# design.net
KiCad netlist of a schematic drawn in EAGLE
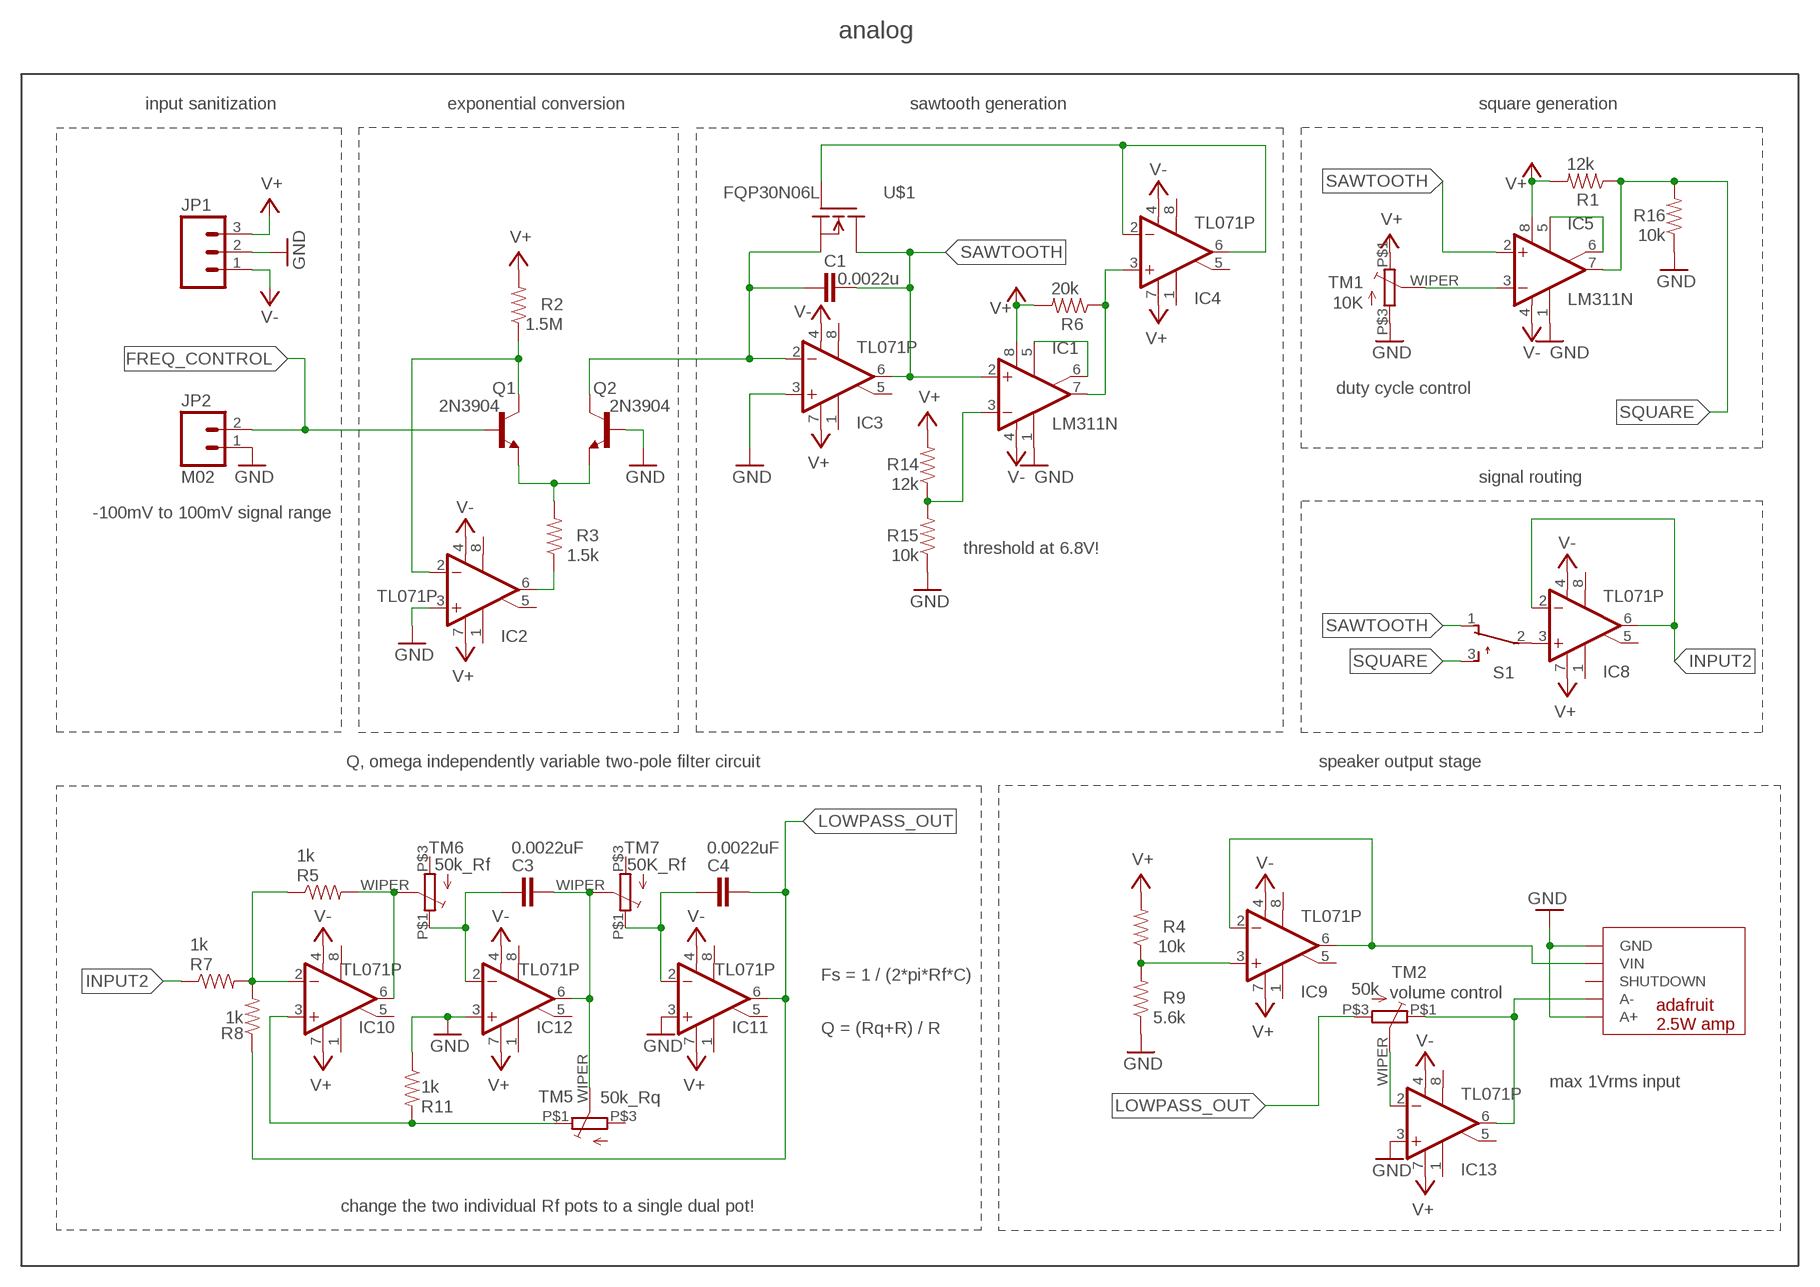
[diagram p0: schematic, sheet 1]

(export (version "E")
  (design (tool "Eeschema 10.0.6"))
  (components
    (comp (ref "C1")
      (value "0.0022u")
      (footprint "eagle-import:3872_WIMA_CAP")
      (libsource (lib "eagle-import") (part "CAPCAP_WIMA"))
    )
    (comp (ref "C3")
      (value "0.0022uF")
      (footprint "eagle-import:CAP-PTH-5MM")
      (libsource (lib "eagle-import") (part "CAPPTH1"))
    )
    (comp (ref "C4")
      (value "0.0022uF")
      (footprint "eagle-import:CAP-PTH-5MM")
      (libsource (lib "eagle-import") (part "CAPPTH1"))
    )
    (comp (ref "IC1")
      (value "LM311N")
      (footprint "eagle-import:DIL08")
      (libsource (lib "eagle-import") (part "LM311N"))
    )
    (comp (ref "IC2")
      (value "TL071P")
      (footprint "eagle-import:DIL08")
      (libsource (lib "eagle-import") (part "TL071P"))
    )
    (comp (ref "IC3")
      (value "TL071P")
      (footprint "eagle-import:DIL08")
      (libsource (lib "eagle-import") (part "TL071P"))
    )
    (comp (ref "IC4")
      (value "TL071P")
      (footprint "eagle-import:DIL08")
      (libsource (lib "eagle-import") (part "TL071P"))
    )
    (comp (ref "IC5")
      (value "LM311N")
      (footprint "eagle-import:DIL08")
      (libsource (lib "eagle-import") (part "LM311N"))
    )
    (comp (ref "IC8")
      (value "TL071P")
      (footprint "eagle-import:DIL08")
      (libsource (lib "eagle-import") (part "TL071P"))
    )
    (comp (ref "IC9")
      (value "TL071P")
      (footprint "eagle-import:DIL08")
      (libsource (lib "eagle-import") (part "TL071P"))
    )
    (comp (ref "IC10")
      (value "TL071P")
      (footprint "eagle-import:DIL08")
      (libsource (lib "eagle-import") (part "TL071P"))
    )
    (comp (ref "IC11")
      (value "TL071P")
      (footprint "eagle-import:DIL08")
      (libsource (lib "eagle-import") (part "TL071P"))
    )
    (comp (ref "IC12")
      (value "TL071P")
      (footprint "eagle-import:DIL08")
      (libsource (lib "eagle-import") (part "TL071P"))
    )
    (comp (ref "IC13")
      (value "TL071P")
      (footprint "eagle-import:DIL08")
      (libsource (lib "eagle-import") (part "TL071P"))
    )
    (comp (ref "JP1")
      (value "M03")
      (footprint "eagle-import:1X03")
      (libsource (lib "eagle-import") (part "M03"))
    )
    (comp (ref "JP2")
      (value "M02")
      (footprint "eagle-import:1X02")
      (libsource (lib "eagle-import") (part "M02"))
    )
    (comp (ref "Q1")
      (value "2N3904")
      (footprint "eagle-import:TO92")
      (libsource (lib "eagle-import") (part "2N3904"))
    )
    (comp (ref "Q2")
      (value "2N3904")
      (footprint "eagle-import:TO92")
      (libsource (lib "eagle-import") (part "2N3904"))
    )
    (comp (ref "R1")
      (value "12k")
      (footprint "eagle-import:AXIAL-0.3")
      (libsource (lib "eagle-import") (part "RESISTORAXIAL-0.3"))
    )
    (comp (ref "R2")
      (value "1.5M")
      (footprint "eagle-import:AXIAL-0.3")
      (libsource (lib "eagle-import") (part "RESISTORAXIAL-0.3"))
    )
    (comp (ref "R3")
      (value "1.5k")
      (footprint "eagle-import:AXIAL-0.3")
      (libsource (lib "eagle-import") (part "RESISTORAXIAL-0.3"))
    )
    (comp (ref "R4")
      (value "10k")
      (footprint "eagle-import:AXIAL-0.3")
      (libsource (lib "eagle-import") (part "RESISTORAXIAL-0.3"))
    )
    (comp (ref "R5")
      (value "1k")
      (footprint "eagle-import:AXIAL-0.3")
      (libsource (lib "eagle-import") (part "RESISTORAXIAL-0.3"))
    )
    (comp (ref "R6")
      (value "20k")
      (footprint "eagle-import:AXIAL-0.3")
      (libsource (lib "eagle-import") (part "RESISTORAXIAL-0.3"))
    )
    (comp (ref "R7")
      (value "1k")
      (footprint "eagle-import:AXIAL-0.3")
      (libsource (lib "eagle-import") (part "RESISTORAXIAL-0.3"))
    )
    (comp (ref "R8")
      (value "1k")
      (footprint "eagle-import:AXIAL-0.3")
      (libsource (lib "eagle-import") (part "RESISTORAXIAL-0.3"))
    )
    (comp (ref "R9")
      (value "5.6k")
      (footprint "eagle-import:AXIAL-0.3")
      (libsource (lib "eagle-import") (part "RESISTORAXIAL-0.3"))
    )
    (comp (ref "R11")
      (value "1k")
      (footprint "eagle-import:AXIAL-0.3")
      (libsource (lib "eagle-import") (part "RESISTORAXIAL-0.3"))
    )
    (comp (ref "R14")
      (value "12k")
      (footprint "eagle-import:AXIAL-0.3")
      (libsource (lib "eagle-import") (part "RESISTORAXIAL-0.3"))
    )
    (comp (ref "R15")
      (value "10k")
      (footprint "eagle-import:AXIAL-0.3")
      (libsource (lib "eagle-import") (part "RESISTORAXIAL-0.3"))
    )
    (comp (ref "R16")
      (value "10k")
      (footprint "eagle-import:AXIAL-0.3")
      (libsource (lib "eagle-import") (part "RESISTORAXIAL-0.3"))
    )
    (comp (ref "S1")
      (value "TL32PO")
      (footprint "eagle-import:TL3XPO")
      (libsource (lib "eagle-import") (part "TL32PO"))
    )
    (comp (ref "TM1")
      (value "10K")
      (footprint "eagle-import:3386_TRI")
      (libsource (lib "eagle-import") (part "TRIMPOT"))
    )
    (comp (ref "TM2")
      (value "50k")
      (footprint "eagle-import:3386_TRI")
      (libsource (lib "eagle-import") (part "TRIMPOT"))
    )
    (comp (ref "TM5")
      (value "50k_Rq")
      (footprint "eagle-import:3386_TRI")
      (libsource (lib "eagle-import") (part "TRIMPOT"))
    )
    (comp (ref "TM6")
      (value "50k_Rf")
      (footprint "eagle-import:3386_TRI")
      (libsource (lib "eagle-import") (part "TRIMPOT"))
    )
    (comp (ref "TM7")
      (value "50K_Rf")
      (footprint "eagle-import:3386_TRI")
      (libsource (lib "eagle-import") (part "TRIMPOT"))
    )
    (comp (ref "U$1")
      (value "FQP30N06L")
      (footprint "eagle-import:TO-220")
      (libsource (lib "eagle-import") (part "FQP30N06L"))
    )
    (comp (ref "U$2")
      (value "PAM8302A_ADAFRUIT")
      (footprint "eagle-import:PAM8302A_ADAFRUIT")
      (libsource (lib "eagle-import") (part "PAM8302A_ADAFRUIT"))
    )
  )
  (nets
    (net (code "1") (name "FREQ_CONTROL") (class "Default")
      (node (ref "JP2") (pin "2") (pinfunction "2_2") (pintype "passive"))
      (node (ref "Q1") (pin "2") (pinfunction "B_2") (pintype "passive"))
    )
    (net (code "2") (name "GND") (class "Default")
      (node (ref "IC1") (pin "1") (pinfunction "GND_1") (pintype "passive"))
      (node (ref "IC11") (pin "3") (pinfunction "+IN_3") (pintype "input"))
      (node (ref "IC12") (pin "3") (pinfunction "+IN_3") (pintype "input"))
      (node (ref "IC13") (pin "3") (pinfunction "+IN_3") (pintype "input"))
      (node (ref "IC2") (pin "3") (pinfunction "+IN_3") (pintype "input"))
      (node (ref "IC3") (pin "3") (pinfunction "+IN_3") (pintype "input"))
      (node (ref "IC5") (pin "1") (pinfunction "GND_1") (pintype "passive"))
      (node (ref "JP1") (pin "2") (pinfunction "2_2") (pintype "passive"))
      (node (ref "JP2") (pin "1") (pinfunction "1_1") (pintype "passive"))
      (node (ref "Q2") (pin "2") (pinfunction "B_2") (pintype "passive"))
      (node (ref "R11") (pin "P$1") (pinfunction "1_P$1") (pintype "passive"))
      (node (ref "R15") (pin "P$1") (pinfunction "1_P$1") (pintype "passive"))
      (node (ref "R16") (pin "P$1") (pinfunction "1_P$1") (pintype "passive"))
      (node (ref "R9") (pin "P$1") (pinfunction "1_P$1") (pintype "passive"))
      (node (ref "TM1") (pin "P$3") (pinfunction "A_P$3") (pintype "passive"))
      (node (ref "U$2") (pin "A+") (pinfunction "A+_A+") (pintype "bidirectional"))
      (node (ref "U$2") (pin "GND") (pinfunction "GND_GND") (pintype "bidirectional"))
    )
    (net (code "3") (name "INPUT2") (class "Default")
      (node (ref "IC8") (pin "2") (pinfunction "-IN_2") (pintype "input"))
      (node (ref "IC8") (pin "6") (pinfunction "OUT_6") (pintype "output"))
      (node (ref "R7") (pin "P$1") (pinfunction "1_P$1") (pintype "passive"))
    )
    (net (code "4") (name "LOWPASS_OUT") (class "Default")
      (node (ref "C4") (pin "1") (pinfunction "1_1") (pintype "passive"))
      (node (ref "IC11") (pin "6") (pinfunction "OUT_6") (pintype "output"))
      (node (ref "R8") (pin "P$1") (pinfunction "1_P$1") (pintype "passive"))
      (node (ref "TM2") (pin "P$3") (pinfunction "A_P$3") (pintype "passive"))
    )
    (net (code "5") (name "Net-(C1-1)") (class "Default")
      (node (ref "C1") (pin "P$1") (pinfunction "1_P$1") (pintype "passive"))
      (node (ref "IC3") (pin "2") (pinfunction "-IN_2") (pintype "input"))
      (node (ref "Q2") (pin "1") (pinfunction "C_1") (pintype "passive"))
      (node (ref "U$1") (pin "3") (pinfunction "S_3") (pintype "passive"))
    )
    (net (code "6") (name "Net-(IC1--IN)") (class "Default")
      (node (ref "IC1") (pin "3") (pinfunction "-IN_3") (pintype "input"))
      (node (ref "R14") (pin "P$1") (pinfunction "1_P$1") (pintype "passive"))
      (node (ref "R15") (pin "P$2") (pinfunction "2_P$2") (pintype "passive"))
    )
    (net (code "7") (name "Net-(IC1-ON)") (class "Default")
      (node (ref "IC1") (pin "5") (pinfunction "ON_5") (pintype "passive"))
      (node (ref "IC1") (pin "6") (pinfunction "ON/STR_6") (pintype "passive"))
    )
    (net (code "8") (name "Net-(IC1-OUT)") (class "Default")
      (node (ref "IC1") (pin "7") (pinfunction "OUT_7") (pintype "output"))
      (node (ref "IC4") (pin "3") (pinfunction "+IN_3") (pintype "input"))
      (node (ref "R6") (pin "P$1") (pinfunction "1_P$1") (pintype "passive"))
    )
    (net (code "9") (name "Net-(IC2--IN)") (class "Default")
      (node (ref "IC2") (pin "2") (pinfunction "-IN_2") (pintype "input"))
      (node (ref "Q1") (pin "1") (pinfunction "C_1") (pintype "passive"))
      (node (ref "R2") (pin "P$1") (pinfunction "1_P$1") (pintype "passive"))
    )
    (net (code "10") (name "Net-(IC2-OUT)") (class "Default")
      (node (ref "IC2") (pin "6") (pinfunction "OUT_6") (pintype "output"))
      (node (ref "R3") (pin "P$1") (pinfunction "1_P$1") (pintype "passive"))
    )
    (net (code "11") (name "Net-(IC4--IN)") (class "Default")
      (node (ref "IC4") (pin "2") (pinfunction "-IN_2") (pintype "input"))
      (node (ref "IC4") (pin "6") (pinfunction "OUT_6") (pintype "output"))
      (node (ref "U$1") (pin "1") (pinfunction "G_1") (pintype "passive"))
    )
    (net (code "12") (name "Net-(IC5--IN)") (class "Default")
      (node (ref "IC5") (pin "3") (pinfunction "-IN_3") (pintype "input"))
      (node (ref "TM1") (pin "WIPER") (pinfunction "S_WIPER") (pintype "passive"))
    )
    (net (code "13") (name "Net-(IC5-ON)") (class "Default")
      (node (ref "IC5") (pin "5") (pinfunction "ON_5") (pintype "passive"))
      (node (ref "IC5") (pin "6") (pinfunction "ON/STR_6") (pintype "passive"))
    )
    (net (code "14") (name "Net-(IC8-+IN)") (class "Default")
      (node (ref "IC8") (pin "3") (pinfunction "+IN_3") (pintype "input"))
      (node (ref "S1") (pin "2") (pinfunction "P_2") (pintype "passive"))
    )
    (net (code "15") (name "Net-(IC9-+IN)") (class "Default")
      (node (ref "IC9") (pin "3") (pinfunction "+IN_3") (pintype "input"))
      (node (ref "R4") (pin "P$1") (pinfunction "1_P$1") (pintype "passive"))
      (node (ref "R9") (pin "P$2") (pinfunction "2_P$2") (pintype "passive"))
    )
    (net (code "16") (name "Net-(IC9--IN)") (class "Default")
      (node (ref "IC9") (pin "2") (pinfunction "-IN_2") (pintype "input"))
      (node (ref "IC9") (pin "6") (pinfunction "OUT_6") (pintype "output"))
      (node (ref "U$2") (pin "VIN") (pinfunction "VIN_VIN") (pintype "bidirectional"))
    )
    (net (code "17") (name "Net-(IC10-+IN)") (class "Default")
      (node (ref "IC10") (pin "3") (pinfunction "+IN_3") (pintype "input"))
      (node (ref "R11") (pin "P$2") (pinfunction "2_P$2") (pintype "passive"))
      (node (ref "TM5") (pin "P$1") (pinfunction "E_P$1") (pintype "passive"))
    )
    (net (code "18") (name "Net-(IC10--IN)") (class "Default")
      (node (ref "IC10") (pin "2") (pinfunction "-IN_2") (pintype "input"))
      (node (ref "R5") (pin "P$1") (pinfunction "1_P$1") (pintype "passive"))
      (node (ref "R7") (pin "P$2") (pinfunction "2_P$2") (pintype "passive"))
      (node (ref "R8") (pin "P$2") (pinfunction "2_P$2") (pintype "passive"))
    )
    (net (code "19") (name "Net-(IC10-OUT)") (class "Default")
      (node (ref "IC10") (pin "6") (pinfunction "OUT_6") (pintype "output"))
      (node (ref "R5") (pin "P$2") (pinfunction "2_P$2") (pintype "passive"))
      (node (ref "TM6") (pin "WIPER") (pinfunction "S_WIPER") (pintype "passive"))
    )
    (net (code "20") (name "Net-(IC11--IN)") (class "Default")
      (node (ref "C4") (pin "2") (pinfunction "2_2") (pintype "passive"))
      (node (ref "IC11") (pin "2") (pinfunction "-IN_2") (pintype "input"))
      (node (ref "TM7") (pin "P$1") (pinfunction "E_P$1") (pintype "passive"))
    )
    (net (code "21") (name "Net-(IC12--IN)") (class "Default")
      (node (ref "C3") (pin "2") (pinfunction "2_2") (pintype "passive"))
      (node (ref "IC12") (pin "2") (pinfunction "-IN_2") (pintype "input"))
      (node (ref "TM6") (pin "P$1") (pinfunction "E_P$1") (pintype "passive"))
    )
    (net (code "22") (name "Net-(IC12-OUT)") (class "Default")
      (node (ref "C3") (pin "1") (pinfunction "1_1") (pintype "passive"))
      (node (ref "IC12") (pin "6") (pinfunction "OUT_6") (pintype "output"))
      (node (ref "TM5") (pin "WIPER") (pinfunction "S_WIPER") (pintype "passive"))
      (node (ref "TM7") (pin "WIPER") (pinfunction "S_WIPER") (pintype "passive"))
    )
    (net (code "23") (name "Net-(IC13--IN)") (class "Default")
      (node (ref "IC13") (pin "2") (pinfunction "-IN_2") (pintype "input"))
      (node (ref "TM2") (pin "WIPER") (pinfunction "S_WIPER") (pintype "passive"))
    )
    (net (code "24") (name "Net-(IC13-OUT)") (class "Default")
      (node (ref "IC13") (pin "6") (pinfunction "OUT_6") (pintype "output"))
      (node (ref "TM2") (pin "P$1") (pinfunction "E_P$1") (pintype "passive"))
      (node (ref "U$2") (pin "A-") (pinfunction "A-_A-") (pintype "bidirectional"))
    )
    (net (code "25") (name "Net-(Q1-E)") (class "Default")
      (node (ref "Q1") (pin "3") (pinfunction "E_3") (pintype "passive"))
      (node (ref "Q2") (pin "3") (pinfunction "E_3") (pintype "passive"))
      (node (ref "R3") (pin "P$2") (pinfunction "2_P$2") (pintype "passive"))
    )
    (net (code "26") (name "SAWTOOTH") (class "Default")
      (node (ref "C1") (pin "P$5") (pinfunction "2_P$5") (pintype "passive"))
      (node (ref "IC1") (pin "2") (pinfunction "+IN_2") (pintype "input"))
      (node (ref "IC3") (pin "6") (pinfunction "OUT_6") (pintype "output"))
      (node (ref "IC5") (pin "2") (pinfunction "+IN_2") (pintype "input"))
      (node (ref "S1") (pin "1") (pinfunction "O_1") (pintype "passive"))
      (node (ref "U$1") (pin "2") (pinfunction "D_2") (pintype "passive"))
    )
    (net (code "27") (name "SQUARE") (class "Default")
      (node (ref "IC5") (pin "7") (pinfunction "OUT_7") (pintype "output"))
      (node (ref "R1") (pin "P$1") (pinfunction "1_P$1") (pintype "passive"))
      (node (ref "R16") (pin "P$2") (pinfunction "2_P$2") (pintype "passive"))
      (node (ref "S1") (pin "3") (pinfunction "S_3") (pintype "passive"))
    )
    (net (code "28") (name "V+") (class "Default")
      (node (ref "IC1") (pin "8") (pinfunction "V+_8") (pintype "power_in"))
      (node (ref "IC10") (pin "7") (pinfunction "V+_7") (pintype "power_in"))
      (node (ref "IC11") (pin "7") (pinfunction "V+_7") (pintype "power_in"))
      (node (ref "IC12") (pin "7") (pinfunction "V+_7") (pintype "power_in"))
      (node (ref "IC13") (pin "7") (pinfunction "V+_7") (pintype "power_in"))
      (node (ref "IC2") (pin "7") (pinfunction "V+_7") (pintype "power_in"))
      (node (ref "IC3") (pin "7") (pinfunction "V+_7") (pintype "power_in"))
      (node (ref "IC4") (pin "7") (pinfunction "V+_7") (pintype "power_in"))
      (node (ref "IC5") (pin "8") (pinfunction "V+_8") (pintype "power_in"))
      (node (ref "IC8") (pin "7") (pinfunction "V+_7") (pintype "power_in"))
      (node (ref "IC9") (pin "7") (pinfunction "V+_7") (pintype "power_in"))
      (node (ref "JP1") (pin "3") (pinfunction "3_3") (pintype "passive"))
      (node (ref "R1") (pin "P$2") (pinfunction "2_P$2") (pintype "passive"))
      (node (ref "R14") (pin "P$2") (pinfunction "2_P$2") (pintype "passive"))
      (node (ref "R2") (pin "P$2") (pinfunction "2_P$2") (pintype "passive"))
      (node (ref "R4") (pin "P$2") (pinfunction "2_P$2") (pintype "passive"))
      (node (ref "R6") (pin "P$2") (pinfunction "2_P$2") (pintype "passive"))
      (node (ref "TM1") (pin "P$1") (pinfunction "E_P$1") (pintype "passive"))
    )
    (net (code "29") (name "V-") (class "Default")
      (node (ref "IC1") (pin "4") (pinfunction "V-_4") (pintype "power_in"))
      (node (ref "IC10") (pin "4") (pinfunction "V-_4") (pintype "power_in"))
      (node (ref "IC11") (pin "4") (pinfunction "V-_4") (pintype "power_in"))
      (node (ref "IC12") (pin "4") (pinfunction "V-_4") (pintype "power_in"))
      (node (ref "IC13") (pin "4") (pinfunction "V-_4") (pintype "power_in"))
      (node (ref "IC2") (pin "4") (pinfunction "V-_4") (pintype "power_in"))
      (node (ref "IC3") (pin "4") (pinfunction "V-_4") (pintype "power_in"))
      (node (ref "IC4") (pin "4") (pinfunction "V-_4") (pintype "power_in"))
      (node (ref "IC5") (pin "4") (pinfunction "V-_4") (pintype "power_in"))
      (node (ref "IC8") (pin "4") (pinfunction "V-_4") (pintype "power_in"))
      (node (ref "IC9") (pin "4") (pinfunction "V-_4") (pintype "power_in"))
      (node (ref "JP1") (pin "1") (pinfunction "1_1") (pintype "passive"))
    )
    (net (code "30") (name "unconnected-(IC2-ON1-Pad1)") (class "Default")
      (node (ref "IC2") (pin "1") (pinfunction "ON1_1") (pintype "passive"))
    )
    (net (code "31") (name "unconnected-(IC2-ON2-Pad5)") (class "Default")
      (node (ref "IC2") (pin "5") (pinfunction "ON2_5") (pintype "passive"))
    )
    (net (code "32") (name "unconnected-(IC2-OPT-Pad8)") (class "Default")
      (node (ref "IC2") (pin "8") (pinfunction "OPT_8") (pintype "passive"))
    )
    (net (code "33") (name "unconnected-(IC3-ON1-Pad1)") (class "Default")
      (node (ref "IC3") (pin "1") (pinfunction "ON1_1") (pintype "passive"))
    )
    (net (code "34") (name "unconnected-(IC3-ON2-Pad5)") (class "Default")
      (node (ref "IC3") (pin "5") (pinfunction "ON2_5") (pintype "passive"))
    )
    (net (code "35") (name "unconnected-(IC3-OPT-Pad8)") (class "Default")
      (node (ref "IC3") (pin "8") (pinfunction "OPT_8") (pintype "passive"))
    )
    (net (code "36") (name "unconnected-(IC4-ON1-Pad1)") (class "Default")
      (node (ref "IC4") (pin "1") (pinfunction "ON1_1") (pintype "passive"))
    )
    (net (code "37") (name "unconnected-(IC4-ON2-Pad5)") (class "Default")
      (node (ref "IC4") (pin "5") (pinfunction "ON2_5") (pintype "passive"))
    )
    (net (code "38") (name "unconnected-(IC4-OPT-Pad8)") (class "Default")
      (node (ref "IC4") (pin "8") (pinfunction "OPT_8") (pintype "passive"))
    )
    (net (code "39") (name "unconnected-(IC8-ON1-Pad1)") (class "Default")
      (node (ref "IC8") (pin "1") (pinfunction "ON1_1") (pintype "passive"))
    )
    (net (code "40") (name "unconnected-(IC8-ON2-Pad5)") (class "Default")
      (node (ref "IC8") (pin "5") (pinfunction "ON2_5") (pintype "passive"))
    )
    (net (code "41") (name "unconnected-(IC8-OPT-Pad8)") (class "Default")
      (node (ref "IC8") (pin "8") (pinfunction "OPT_8") (pintype "passive"))
    )
    (net (code "42") (name "unconnected-(IC9-ON1-Pad1)") (class "Default")
      (node (ref "IC9") (pin "1") (pinfunction "ON1_1") (pintype "passive"))
    )
    (net (code "43") (name "unconnected-(IC9-ON2-Pad5)") (class "Default")
      (node (ref "IC9") (pin "5") (pinfunction "ON2_5") (pintype "passive"))
    )
    (net (code "44") (name "unconnected-(IC9-OPT-Pad8)") (class "Default")
      (node (ref "IC9") (pin "8") (pinfunction "OPT_8") (pintype "passive"))
    )
    (net (code "45") (name "unconnected-(IC10-ON1-Pad1)") (class "Default")
      (node (ref "IC10") (pin "1") (pinfunction "ON1_1") (pintype "passive"))
    )
    (net (code "46") (name "unconnected-(IC10-ON2-Pad5)") (class "Default")
      (node (ref "IC10") (pin "5") (pinfunction "ON2_5") (pintype "passive"))
    )
    (net (code "47") (name "unconnected-(IC10-OPT-Pad8)") (class "Default")
      (node (ref "IC10") (pin "8") (pinfunction "OPT_8") (pintype "passive"))
    )
    (net (code "48") (name "unconnected-(IC11-ON1-Pad1)") (class "Default")
      (node (ref "IC11") (pin "1") (pinfunction "ON1_1") (pintype "passive"))
    )
    (net (code "49") (name "unconnected-(IC11-ON2-Pad5)") (class "Default")
      (node (ref "IC11") (pin "5") (pinfunction "ON2_5") (pintype "passive"))
    )
    (net (code "50") (name "unconnected-(IC11-OPT-Pad8)") (class "Default")
      (node (ref "IC11") (pin "8") (pinfunction "OPT_8") (pintype "passive"))
    )
    (net (code "51") (name "unconnected-(IC12-ON1-Pad1)") (class "Default")
      (node (ref "IC12") (pin "1") (pinfunction "ON1_1") (pintype "passive"))
    )
    (net (code "52") (name "unconnected-(IC12-ON2-Pad5)") (class "Default")
      (node (ref "IC12") (pin "5") (pinfunction "ON2_5") (pintype "passive"))
    )
    (net (code "53") (name "unconnected-(IC12-OPT-Pad8)") (class "Default")
      (node (ref "IC12") (pin "8") (pinfunction "OPT_8") (pintype "passive"))
    )
    (net (code "54") (name "unconnected-(IC13-ON1-Pad1)") (class "Default")
      (node (ref "IC13") (pin "1") (pinfunction "ON1_1") (pintype "passive"))
    )
    (net (code "55") (name "unconnected-(IC13-ON2-Pad5)") (class "Default")
      (node (ref "IC13") (pin "5") (pinfunction "ON2_5") (pintype "passive"))
    )
    (net (code "56") (name "unconnected-(IC13-OPT-Pad8)") (class "Default")
      (node (ref "IC13") (pin "8") (pinfunction "OPT_8") (pintype "passive"))
    )
    (net (code "57") (name "unconnected-(TM5-A-PadP$3)") (class "Default")
      (node (ref "TM5") (pin "P$3") (pinfunction "A_P$3") (pintype "passive"))
    )
    (net (code "58") (name "unconnected-(TM6-A-PadP$3)") (class "Default")
      (node (ref "TM6") (pin "P$3") (pinfunction "A_P$3") (pintype "passive"))
    )
    (net (code "59") (name "unconnected-(TM7-A-PadP$3)") (class "Default")
      (node (ref "TM7") (pin "P$3") (pinfunction "A_P$3") (pintype "passive"))
    )
    (net (code "60") (name "unconnected-(U$2-SHUTDOWN-PadSD)") (class "Default")
      (node (ref "U$2") (pin "SD") (pinfunction "SHUTDOWN_SD") (pintype "bidirectional"))
    )
  )
)
